# DHT_Board-v_1_1.net
KiCad netlist of a schematic drawn in EAGLE
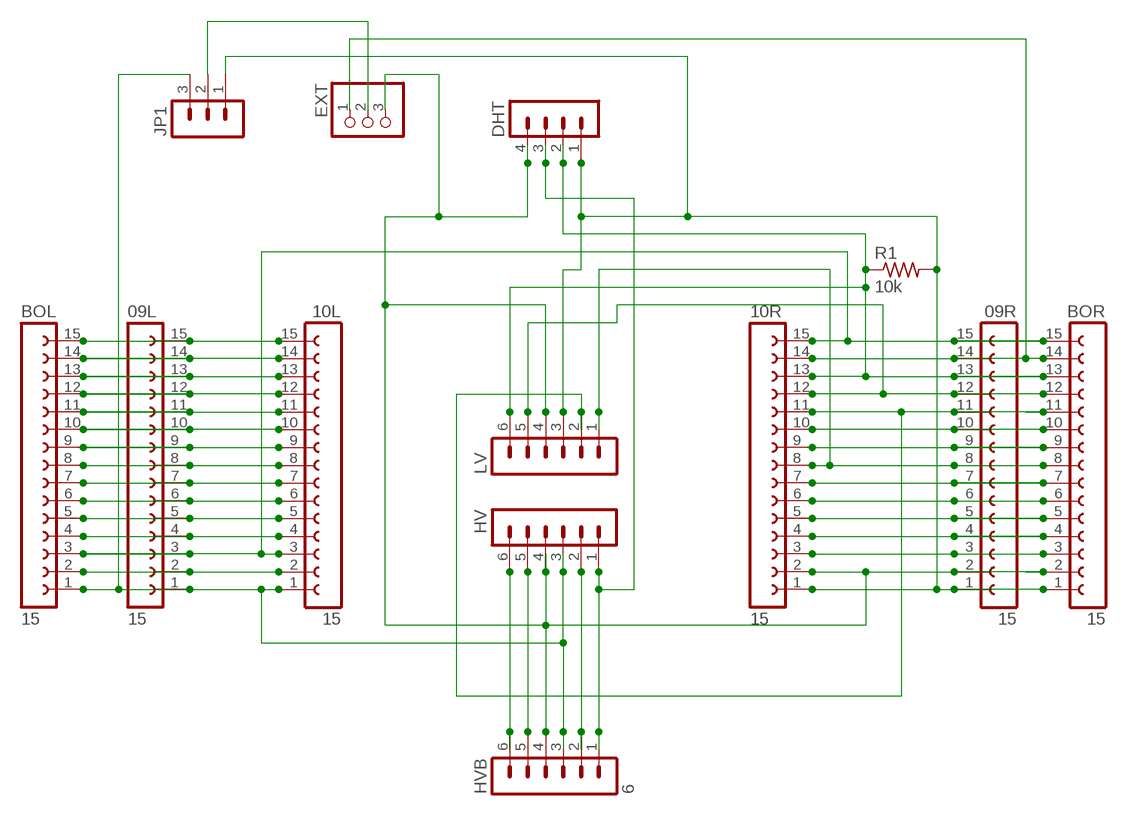
[diagram p0: schematic, sheet 1]

(export (version "E")
  (design (tool "Eeschema 10.0.6"))
  (components
    (comp (ref "09L")
      (value "15")
      (footprint "eagle-import:FE15")
      (libsource (lib "eagle-import") (part "FE15-1"))
    )
    (comp (ref "09R")
      (value "15")
      (footprint "eagle-import:FE15")
      (libsource (lib "eagle-import") (part "FE15-1"))
    )
    (comp (ref "10L")
      (value "15")
      (footprint "eagle-import:FE15")
      (libsource (lib "eagle-import") (part "FE15-1"))
    )
    (comp (ref "10R")
      (value "15")
      (footprint "eagle-import:FE15")
      (libsource (lib "eagle-import") (part "FE15-1"))
    )
    (comp (ref "BOL")
      (value "15")
      (footprint "eagle-import:FE15")
      (libsource (lib "eagle-import") (part "FE15-1"))
    )
    (comp (ref "BOR")
      (value "15")
      (footprint "eagle-import:FE15")
      (libsource (lib "eagle-import") (part "FE15-1"))
    )
    (comp (ref "DHT")
      (value "MA04-1")
      (footprint "eagle-import:MA04-1")
      (libsource (lib "eagle-import") (part "MA04-1"))
    )
    (comp (ref "EXT")
      (value "PINHD-1X3")
      (footprint "eagle-import:1X03")
      (libsource (lib "eagle-import") (part "PINHD-1X3"))
    )
    (comp (ref "HV")
      (value "MA06-1")
      (footprint "eagle-import:MA06-1")
      (libsource (lib "eagle-import") (part "MA06-1"))
    )
    (comp (ref "HVB")
      (value "6")
      (footprint "eagle-import:MA06-1")
      (libsource (lib "eagle-import") (part "MA06-1"))
    )
    (comp (ref "JP1")
      (value "MA03-1")
      (footprint "eagle-import:MA03-1")
      (libsource (lib "eagle-import") (part "MA03-1"))
    )
    (comp (ref "LV")
      (value "MA06-1")
      (footprint "eagle-import:MA06-1")
      (libsource (lib "eagle-import") (part "MA06-1"))
    )
    (comp (ref "R1")
      (value "10k")
      (footprint "eagle-import:0207_10")
      (libsource (lib "eagle-import") (part "R-US_0207/10"))
    )
  )
  (nets
    (net (code "1") (name "/3.3V") (class "Default")
      (node (ref "09R") (pin "1") (pinfunction "1_1") (pintype "passive"))
      (node (ref "09R") (pin "10") (pinfunction "10_10") (pintype "passive"))
      (node (ref "10R") (pin "1") (pinfunction "1_1") (pintype "passive"))
      (node (ref "10R") (pin "10") (pinfunction "10_10") (pintype "passive"))
      (node (ref "BOR") (pin "1") (pinfunction "1_1") (pintype "passive"))
      (node (ref "BOR") (pin "10") (pinfunction "10_10") (pintype "passive"))
      (node (ref "DHT") (pin "1") (pinfunction "1_1") (pintype "passive"))
      (node (ref "JP1") (pin "1") (pinfunction "1_1") (pintype "passive"))
      (node (ref "LV") (pin "3") (pinfunction "3_3") (pintype "passive"))
      (node (ref "R1") (pin "2") (pinfunction "2_2") (pintype "passive"))
    )
    (net (code "2") (name "/GND") (class "Default")
      (node (ref "09R") (pin "2") (pinfunction "2_2") (pintype "passive"))
      (node (ref "09R") (pin "9") (pinfunction "9_9") (pintype "passive"))
      (node (ref "10R") (pin "2") (pinfunction "2_2") (pintype "passive"))
      (node (ref "10R") (pin "9") (pinfunction "9_9") (pintype "passive"))
      (node (ref "BOR") (pin "2") (pinfunction "2_2") (pintype "passive"))
      (node (ref "BOR") (pin "9") (pinfunction "9_9") (pintype "passive"))
      (node (ref "DHT") (pin "4") (pinfunction "4_4") (pintype "passive"))
      (node (ref "EXT") (pin "3") (pinfunction "3_3") (pintype "passive"))
      (node (ref "HV") (pin "4") (pinfunction "4_4") (pintype "passive"))
      (node (ref "HVB") (pin "4") (pinfunction "4_4") (pintype "passive"))
      (node (ref "LV") (pin "4") (pinfunction "4_4") (pintype "passive"))
    )
    (net (code "3") (name "Net-(09L-Pad1)") (class "Default")
      (node (ref "09L") (pin "1") (pinfunction "1_1") (pintype "passive"))
      (node (ref "10L") (pin "1") (pinfunction "1_1") (pintype "passive"))
      (node (ref "BOL") (pin "1") (pinfunction "1_1") (pintype "passive"))
      (node (ref "HV") (pin "3") (pinfunction "3_3") (pintype "passive"))
      (node (ref "HVB") (pin "3") (pinfunction "3_3") (pintype "passive"))
      (node (ref "JP1") (pin "3") (pinfunction "3_3") (pintype "passive"))
    )
    (net (code "4") (name "Net-(09L-Pad2)") (class "Default")
      (node (ref "09L") (pin "2") (pinfunction "2_2") (pintype "passive"))
      (node (ref "10L") (pin "2") (pinfunction "2_2") (pintype "passive"))
      (node (ref "BOL") (pin "2") (pinfunction "2_2") (pintype "passive"))
    )
    (net (code "5") (name "Net-(09L-Pad3)") (class "Default")
      (node (ref "09L") (pin "3") (pinfunction "3_3") (pintype "passive"))
      (node (ref "09R") (pin "15") (pinfunction "15_15") (pintype "passive"))
      (node (ref "10L") (pin "3") (pinfunction "3_3") (pintype "passive"))
      (node (ref "10R") (pin "15") (pinfunction "15_15") (pintype "passive"))
      (node (ref "BOL") (pin "3") (pinfunction "3_3") (pintype "passive"))
      (node (ref "BOR") (pin "15") (pinfunction "15_15") (pintype "passive"))
    )
    (net (code "6") (name "Net-(09L-Pad4)") (class "Default")
      (node (ref "09L") (pin "4") (pinfunction "4_4") (pintype "passive"))
      (node (ref "10L") (pin "4") (pinfunction "4_4") (pintype "passive"))
      (node (ref "BOL") (pin "4") (pinfunction "4_4") (pintype "passive"))
    )
    (net (code "7") (name "Net-(09L-Pad5)") (class "Default")
      (node (ref "09L") (pin "5") (pinfunction "5_5") (pintype "passive"))
      (node (ref "10L") (pin "5") (pinfunction "5_5") (pintype "passive"))
      (node (ref "BOL") (pin "5") (pinfunction "5_5") (pintype "passive"))
    )
    (net (code "8") (name "Net-(09L-Pad6)") (class "Default")
      (node (ref "09L") (pin "6") (pinfunction "6_6") (pintype "passive"))
      (node (ref "10L") (pin "6") (pinfunction "6_6") (pintype "passive"))
      (node (ref "BOL") (pin "6") (pinfunction "6_6") (pintype "passive"))
    )
    (net (code "9") (name "Net-(09L-Pad7)") (class "Default")
      (node (ref "09L") (pin "7") (pinfunction "7_7") (pintype "passive"))
      (node (ref "10L") (pin "7") (pinfunction "7_7") (pintype "passive"))
      (node (ref "BOL") (pin "7") (pinfunction "7_7") (pintype "passive"))
    )
    (net (code "10") (name "Net-(09L-Pad8)") (class "Default")
      (node (ref "09L") (pin "8") (pinfunction "8_8") (pintype "passive"))
      (node (ref "10L") (pin "8") (pinfunction "8_8") (pintype "passive"))
      (node (ref "BOL") (pin "8") (pinfunction "8_8") (pintype "passive"))
    )
    (net (code "11") (name "Net-(09L-Pad9)") (class "Default")
      (node (ref "09L") (pin "9") (pinfunction "9_9") (pintype "passive"))
      (node (ref "10L") (pin "9") (pinfunction "9_9") (pintype "passive"))
      (node (ref "BOL") (pin "9") (pinfunction "9_9") (pintype "passive"))
    )
    (net (code "12") (name "Net-(09L-Pad10)") (class "Default")
      (node (ref "09L") (pin "10") (pinfunction "10_10") (pintype "passive"))
      (node (ref "10L") (pin "10") (pinfunction "10_10") (pintype "passive"))
      (node (ref "BOL") (pin "10") (pinfunction "10_10") (pintype "passive"))
    )
    (net (code "13") (name "Net-(09L-Pad11)") (class "Default")
      (node (ref "09L") (pin "11") (pinfunction "11_11") (pintype "passive"))
      (node (ref "10L") (pin "11") (pinfunction "11_11") (pintype "passive"))
      (node (ref "BOL") (pin "11") (pinfunction "11_11") (pintype "passive"))
    )
    (net (code "14") (name "Net-(09L-Pad12)") (class "Default")
      (node (ref "09L") (pin "12") (pinfunction "12_12") (pintype "passive"))
      (node (ref "10L") (pin "12") (pinfunction "12_12") (pintype "passive"))
      (node (ref "BOL") (pin "12") (pinfunction "12_12") (pintype "passive"))
    )
    (net (code "15") (name "Net-(09L-Pad13)") (class "Default")
      (node (ref "09L") (pin "13") (pinfunction "13_13") (pintype "passive"))
      (node (ref "10L") (pin "13") (pinfunction "13_13") (pintype "passive"))
      (node (ref "BOL") (pin "13") (pinfunction "13_13") (pintype "passive"))
    )
    (net (code "16") (name "Net-(09L-Pad14)") (class "Default")
      (node (ref "09L") (pin "14") (pinfunction "14_14") (pintype "passive"))
      (node (ref "10L") (pin "14") (pinfunction "14_14") (pintype "passive"))
      (node (ref "BOL") (pin "14") (pinfunction "14_14") (pintype "passive"))
    )
    (net (code "17") (name "Net-(09L-Pad15)") (class "Default")
      (node (ref "09L") (pin "15") (pinfunction "15_15") (pintype "passive"))
      (node (ref "10L") (pin "15") (pinfunction "15_15") (pintype "passive"))
      (node (ref "BOL") (pin "15") (pinfunction "15_15") (pintype "passive"))
    )
    (net (code "18") (name "Net-(09R-Pad3)") (class "Default")
      (node (ref "09R") (pin "3") (pinfunction "3_3") (pintype "passive"))
      (node (ref "10R") (pin "3") (pinfunction "3_3") (pintype "passive"))
      (node (ref "BOR") (pin "3") (pinfunction "3_3") (pintype "passive"))
    )
    (net (code "19") (name "Net-(09R-Pad4)") (class "Default")
      (node (ref "09R") (pin "4") (pinfunction "4_4") (pintype "passive"))
      (node (ref "10R") (pin "4") (pinfunction "4_4") (pintype "passive"))
      (node (ref "BOR") (pin "4") (pinfunction "4_4") (pintype "passive"))
    )
    (net (code "20") (name "Net-(09R-Pad5)") (class "Default")
      (node (ref "09R") (pin "5") (pinfunction "5_5") (pintype "passive"))
      (node (ref "10R") (pin "5") (pinfunction "5_5") (pintype "passive"))
      (node (ref "BOR") (pin "5") (pinfunction "5_5") (pintype "passive"))
    )
    (net (code "21") (name "Net-(09R-Pad6)") (class "Default")
      (node (ref "09R") (pin "6") (pinfunction "6_6") (pintype "passive"))
      (node (ref "10R") (pin "6") (pinfunction "6_6") (pintype "passive"))
      (node (ref "BOR") (pin "6") (pinfunction "6_6") (pintype "passive"))
    )
    (net (code "22") (name "Net-(09R-Pad7)") (class "Default")
      (node (ref "09R") (pin "7") (pinfunction "7_7") (pintype "passive"))
      (node (ref "10R") (pin "7") (pinfunction "7_7") (pintype "passive"))
      (node (ref "BOR") (pin "7") (pinfunction "7_7") (pintype "passive"))
    )
    (net (code "23") (name "Net-(09R-Pad8)") (class "Default")
      (node (ref "09R") (pin "8") (pinfunction "8_8") (pintype "passive"))
      (node (ref "10R") (pin "8") (pinfunction "8_8") (pintype "passive"))
      (node (ref "BOR") (pin "8") (pinfunction "8_8") (pintype "passive"))
      (node (ref "LV") (pin "1") (pinfunction "1_1") (pintype "passive"))
    )
    (net (code "24") (name "Net-(09R-Pad11)") (class "Default")
      (node (ref "09R") (pin "11") (pinfunction "11_11") (pintype "passive"))
      (node (ref "10R") (pin "11") (pinfunction "11_11") (pintype "passive"))
      (node (ref "BOR") (pin "11") (pinfunction "11_11") (pintype "passive"))
      (node (ref "LV") (pin "2") (pinfunction "2_2") (pintype "passive"))
    )
    (net (code "25") (name "Net-(09R-Pad12)") (class "Default")
      (node (ref "09R") (pin "12") (pinfunction "12_12") (pintype "passive"))
      (node (ref "10R") (pin "12") (pinfunction "12_12") (pintype "passive"))
      (node (ref "BOR") (pin "12") (pinfunction "12_12") (pintype "passive"))
      (node (ref "LV") (pin "5") (pinfunction "5_5") (pintype "passive"))
    )
    (net (code "26") (name "Net-(09R-Pad13)") (class "Default")
      (node (ref "09R") (pin "13") (pinfunction "13_13") (pintype "passive"))
      (node (ref "10R") (pin "13") (pinfunction "13_13") (pintype "passive"))
      (node (ref "BOR") (pin "13") (pinfunction "13_13") (pintype "passive"))
      (node (ref "DHT") (pin "2") (pinfunction "2_2") (pintype "passive"))
      (node (ref "LV") (pin "6") (pinfunction "6_6") (pintype "passive"))
      (node (ref "R1") (pin "1") (pinfunction "1_1") (pintype "passive"))
    )
    (net (code "27") (name "Net-(09R-Pad14)") (class "Default")
      (node (ref "09R") (pin "14") (pinfunction "14_14") (pintype "passive"))
      (node (ref "10R") (pin "14") (pinfunction "14_14") (pintype "passive"))
      (node (ref "BOR") (pin "14") (pinfunction "14_14") (pintype "passive"))
      (node (ref "EXT") (pin "1") (pinfunction "1_1") (pintype "passive"))
    )
    (net (code "28") (name "Net-(DHT-Pad3)") (class "Default")
      (node (ref "DHT") (pin "3") (pinfunction "3_3") (pintype "passive"))
      (node (ref "HV") (pin "1") (pinfunction "1_1") (pintype "passive"))
      (node (ref "HVB") (pin "1") (pinfunction "1_1") (pintype "passive"))
    )
    (net (code "29") (name "Net-(EXT-Pad2)") (class "Default")
      (node (ref "EXT") (pin "2") (pinfunction "2_2") (pintype "passive"))
      (node (ref "JP1") (pin "2") (pinfunction "2_2") (pintype "passive"))
    )
    (net (code "30") (name "Net-(HV-Pad2)") (class "Default")
      (node (ref "HV") (pin "2") (pinfunction "2_2") (pintype "passive"))
      (node (ref "HVB") (pin "2") (pinfunction "2_2") (pintype "passive"))
    )
    (net (code "31") (name "Net-(HV-Pad5)") (class "Default")
      (node (ref "HV") (pin "5") (pinfunction "5_5") (pintype "passive"))
      (node (ref "HVB") (pin "5") (pinfunction "5_5") (pintype "passive"))
    )
    (net (code "32") (name "Net-(HV-Pad6)") (class "Default")
      (node (ref "HV") (pin "6") (pinfunction "6_6") (pintype "passive"))
      (node (ref "HVB") (pin "6") (pinfunction "6_6") (pintype "passive"))
    )
  )
)
